# MCU.net
KiCad netlist of a schematic drawn in Altium Designer
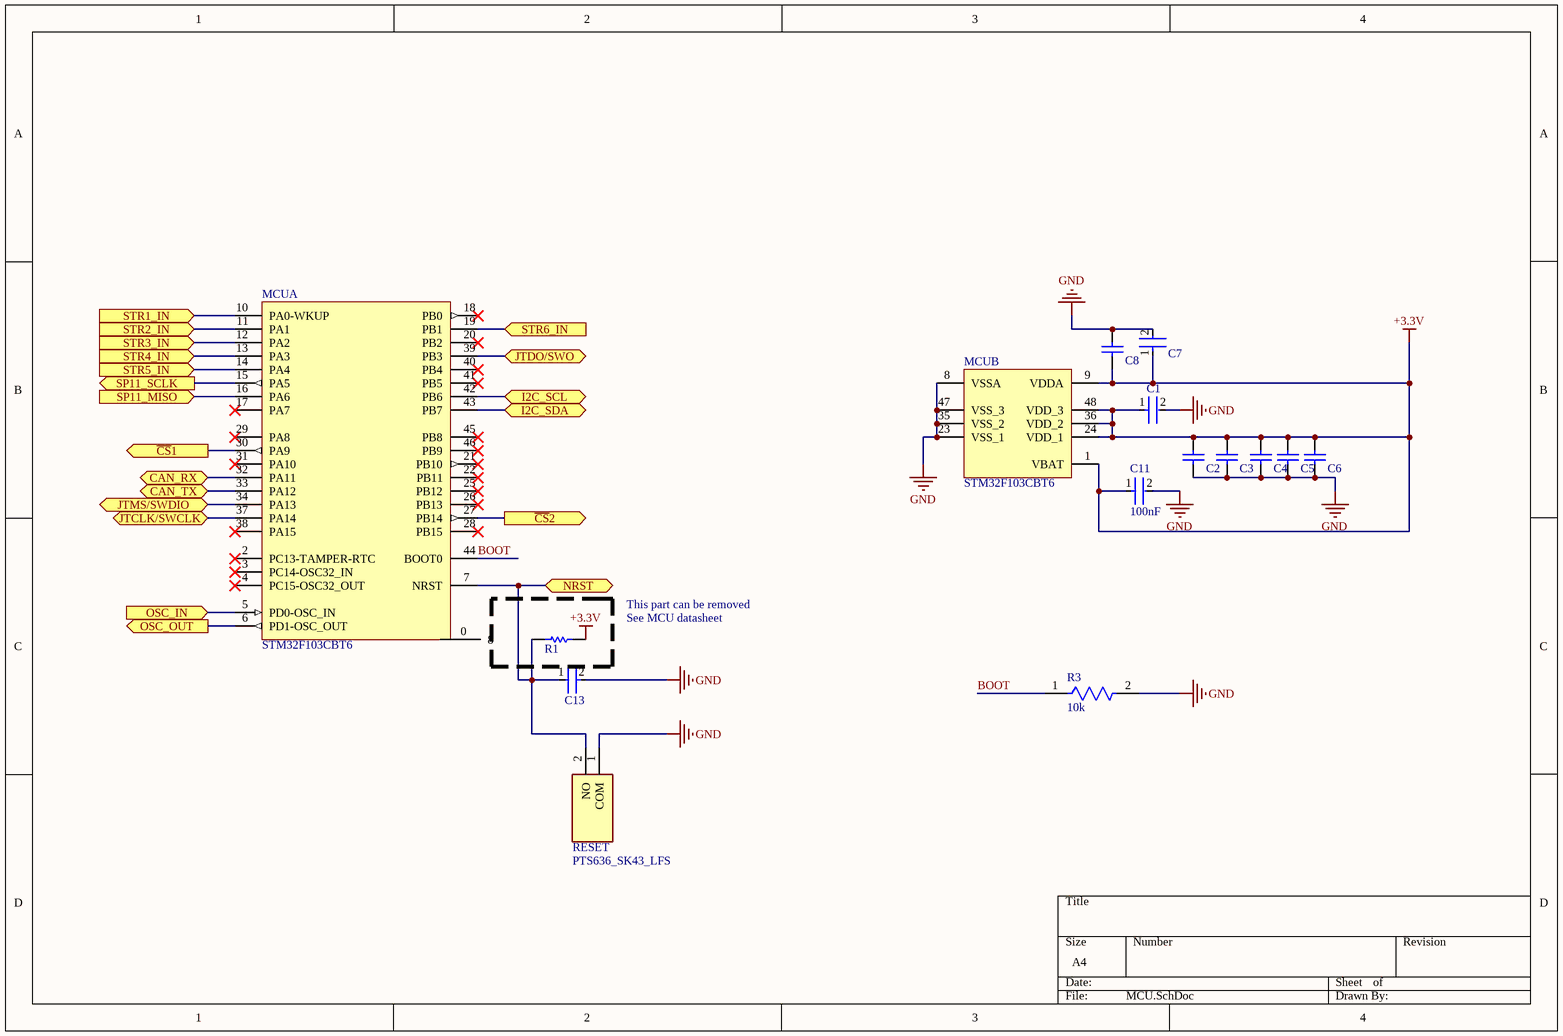
[diagram p0: MCU.SchDoc]

(export (version "E")
  (design (tool "Eeschema 10.0.6"))
  (components
    (comp (ref "C1")
      (value "GRM155R60J475ME47D")
      (footprint "FP-GRM155-0_1-IPC_B")
      (description "Chip Multilayer Ceramic Capacitors for General Purpose, 0402, 4.7uF, X5R, 15%, 20%, 6.3V")
      (fields (field (name "VOLTAGE") "6.3V") (field (name "TOLERANCE") "20%"))
      (libsource (lib "Altium Content Vault") (part "11868f565c42a9108669ba33697ecf6"))
    )
    (comp (ref "C2")
      (value "08051C104KAT2A")
      (footprint "CAPC2013X94X50ML20T25")
      (fields (field (name "MANUFACTURER") "AVX Interconnect / Elco"))
      (libsource (lib "Altium Content Vault") (part "CAP"))
    )
    (comp (ref "C3")
      (value "08051C104KAT2A")
      (footprint "CAPC2013X94X50ML20T25")
      (fields (field (name "MANUFACTURER") "AVX Interconnect / Elco"))
      (libsource (lib "Altium Content Vault") (part "CAP"))
    )
    (comp (ref "C4")
      (value "08051C104KAT2A")
      (footprint "CAPC2013X94X50ML20T25")
      (fields (field (name "MANUFACTURER") "AVX Interconnect / Elco"))
      (libsource (lib "Altium Content Vault") (part "CAP"))
    )
    (comp (ref "C5")
      (value "08051C104KAT2A")
      (footprint "CAPC2013X94X50ML20T25")
      (fields (field (name "MANUFACTURER") "AVX Interconnect / Elco"))
      (libsource (lib "Altium Content Vault") (part "CAP"))
    )
    (comp (ref "C6")
      (value "08051C104KAT2A")
      (footprint "CAPC2013X94X50ML20T25")
      (fields (field (name "MANUFACTURER") "AVX Interconnect / Elco"))
      (libsource (lib "Altium Content Vault") (part "CAP"))
    )
    (comp (ref "C7")
      (value "GRM155R61A105KE15D")
      (footprint "FP-GRM15-0_1-MFG")
      (description "CAP CER 1UF 10V X5R 0402")
      (fields
        (field (name "OCTOPART") "https://octopart.com/grm155r61a105ke15d-murata-197442")
        (field (name "MANUFACTURER") "Murata")
      )
      (libsource (lib "Altium Content Vault") (part "02cd4be3c70576c341d710602a673aa"))
    )
    (comp (ref "C8")
      (value "08051C104KAT2A")
      (footprint "CAPC2013X94X50ML20T25")
      (fields (field (name "MANUFACTURER") "AVX Interconnect / Elco"))
      (libsource (lib "Altium Content Vault") (part "CAP"))
    )
    (comp (ref "C11")
      (value "100nF")
      (footprint "FP-C0402-BB-MFG")
      (description "CAP CER 0.1UF 10V X5R 0402")
      (fields (field (name "MANUFACTURER") "Kemet") (field (name "TOLERANCE") "0.1"))
      (libsource (lib "Altium Content Vault") (part "b4654b650e69147ec39a6b967a45e02"))
    )
    (comp (ref "C13")
      (value "GRM155R71C104KA88D")
      (footprint "FP-GRM15-MFG")
      (description "CAP CER 0.1UF 16V X7R 0402")
      (fields
        (field (name "TOLERANCE") "10%")
        (field (name "OCTOPART") "https://octopart.com/grm155r71c104ka88d-murata-196880")
      )
      (libsource (lib "Altium Content Vault") (part "236180d848d6139a670b325ea6854c9"))
    )
    (comp (ref "MCU")
      (value "STM32F103CBT6")
      (footprint "STM-LQFP48_L")
      (libsource (lib "") (part "MC-ARM-STM32F103X8_B-SQ48_1"))
    )
    (comp (ref "R1")
      (value "CRCW12064K70FKEA")
      (footprint "RESC3216X60X45ML15T20")
      (description "Chip Resistor, 4.7 KOhm, +/- 1%, 0.25 W, -55 to 155 degC, 1206 (3216 Metric), RoHS, Tape and Reel")
      (fields (field (name "MANUFACTURER") "Vishay Semiconductor") (field (name "TOLERANCE") "1%"))
      (libsource (lib "Altium Content Vault") (part "RES-2"))
    )
    (comp (ref "R3")
      (value "10k")
      (footprint "FP-CRCW0402-e3-IPC_B")
      (description "RES SMD 10K OHM 1% 1/16W 0402")
      (fields (field (name "TOLERANCE") "1%"))
      (libsource (lib "Altium Content Vault") (part "1029c3af85768c4190bb7ad29bc67b5"))
    )
    (comp (ref "RESET")
      (value "PTS636_SK43_LFS")
      (footprint "SamacSys:PTS636SK43LFS")
      (description "Switch")
      (fields (field (name "MANUFACTURER_PART_NUMBER") "PTS636 SK43 LFS"))
      (libsource (lib "*") (part "PTS636_SK43_LFS"))
    )
  )
  (nets
    (net (code "1") (name "+3.3V") (class "Default")
      (node (ref "C1") (pin "1") (pinfunction "1_1") (pintype "passive"))
      (node (ref "C11") (pin "1") (pinfunction "1_1") (pintype "passive"))
      (node (ref "C2") (pin "2") (pinfunction "2_2") (pintype "passive"))
      (node (ref "C3") (pin "2") (pinfunction "2_2") (pintype "passive"))
      (node (ref "C4") (pin "2") (pinfunction "2_2") (pintype "passive"))
      (node (ref "C5") (pin "2") (pinfunction "2_2") (pintype "passive"))
      (node (ref "C6") (pin "2") (pinfunction "2_2") (pintype "passive"))
      (node (ref "C7") (pin "1") (pinfunction "1_1") (pintype "passive"))
      (node (ref "C8") (pin "2") (pinfunction "2_2") (pintype "passive"))
      (node (ref "MCU") (pin "1") (pinfunction "VBAT_1") (pintype "power_in"))
      (node (ref "MCU") (pin "24") (pinfunction "VDD_1_24") (pintype "power_in"))
      (node (ref "MCU") (pin "36") (pinfunction "VDD_2_36") (pintype "power_in"))
      (node (ref "MCU") (pin "48") (pinfunction "VDD_3_48") (pintype "power_in"))
      (node (ref "MCU") (pin "9") (pinfunction "VDDA_9") (pintype "power_in"))
      (node (ref "R1") (pin "2") (pinfunction "2_2") (pintype "passive"))
    )
    (net (code "2") (name "/BOOT") (class "Default")
      (node (ref "MCU") (pin "44") (pinfunction "BOOT0_44") (pintype "passive"))
      (node (ref "R3") (pin "1") (pinfunction "1_1") (pintype "passive"))
    )
    (net (code "3") (name "/CAN_RX") (class "Default")
      (node (ref "MCU") (pin "32") (pinfunction "PA11_32") (pintype "passive"))
    )
    (net (code "4") (name "/CAN_TX") (class "Default")
      (node (ref "MCU") (pin "33") (pinfunction "PA12_33") (pintype "passive"))
    )
    (net (code "5") (name "/I2C_SCL") (class "Default")
      (node (ref "MCU") (pin "42") (pinfunction "PB6_42") (pintype "passive"))
    )
    (net (code "6") (name "/I2C_SDA") (class "Default")
      (node (ref "MCU") (pin "43") (pinfunction "PB7_43") (pintype "passive"))
    )
    (net (code "7") (name "/JTCLK{slash}SWCLK") (class "Default")
      (node (ref "MCU") (pin "37") (pinfunction "PA14_37") (pintype "passive"))
    )
    (net (code "8") (name "/JTDO{slash}SWO") (class "Default")
      (node (ref "MCU") (pin "39") (pinfunction "PB3_39") (pintype "passive"))
    )
    (net (code "9") (name "/JTMS{slash}SWDIO") (class "Default")
      (node (ref "MCU") (pin "34") (pinfunction "PA13_34") (pintype "passive"))
    )
    (net (code "10") (name "/NRST") (class "Default")
      (node (ref "C13") (pin "1") (pinfunction "1_1") (pintype "passive"))
      (node (ref "MCU") (pin "7") (pinfunction "NRST_7") (pintype "passive"))
      (node (ref "R1") (pin "1") (pinfunction "1_1") (pintype "passive"))
      (node (ref "RESET") (pin "2") (pinfunction "NO_2") (pintype "passive"))
    )
    (net (code "11") (name "/OSC_IN") (class "Default")
      (node (ref "MCU") (pin "5") (pinfunction "PD0-OSC_IN_5") (pintype "input"))
    )
    (net (code "12") (name "/OSC_OUT") (class "Default")
      (node (ref "MCU") (pin "6") (pinfunction "PD1-OSC_OUT_6") (pintype "output"))
    )
    (net (code "13") (name "/SP11_MISO") (class "Default")
      (node (ref "MCU") (pin "16") (pinfunction "PA6_16") (pintype "passive"))
    )
    (net (code "14") (name "/SP11_SCLK") (class "Default")
      (node (ref "MCU") (pin "15") (pinfunction "PA5_15") (pintype "output"))
    )
    (net (code "15") (name "/STR1_IN") (class "Default")
      (node (ref "MCU") (pin "10") (pinfunction "PA0-WKUP_10") (pintype "passive"))
    )
    (net (code "16") (name "/STR2_IN") (class "Default")
      (node (ref "MCU") (pin "11") (pinfunction "PA1_11") (pintype "passive"))
    )
    (net (code "17") (name "/STR3_IN") (class "Default")
      (node (ref "MCU") (pin "12") (pinfunction "PA2_12") (pintype "passive"))
    )
    (net (code "18") (name "/STR4_IN") (class "Default")
      (node (ref "MCU") (pin "13") (pinfunction "PA3_13") (pintype "passive"))
    )
    (net (code "19") (name "/STR5_IN") (class "Default")
      (node (ref "MCU") (pin "14") (pinfunction "PA4_14") (pintype "passive"))
    )
    (net (code "20") (name "/STR6_IN") (class "Default")
      (node (ref "MCU") (pin "19") (pinfunction "PB1_19") (pintype "passive"))
    )
    (net (code "21") (name "/~{CS}1") (class "Default")
      (node (ref "MCU") (pin "30") (pinfunction "PA9_30") (pintype "output"))
    )
    (net (code "22") (name "/~{CS}2") (class "Default")
      (node (ref "MCU") (pin "27") (pinfunction "PB14_27") (pintype "output"))
    )
    (net (code "23") (name "GND") (class "Default")
      (node (ref "C1") (pin "2") (pinfunction "2_2") (pintype "passive"))
      (node (ref "C11") (pin "2") (pinfunction "2_2") (pintype "passive"))
      (node (ref "C13") (pin "2") (pinfunction "2_2") (pintype "passive"))
      (node (ref "C2") (pin "1") (pinfunction "1_1") (pintype "passive"))
      (node (ref "C3") (pin "1") (pinfunction "1_1") (pintype "passive"))
      (node (ref "C4") (pin "1") (pinfunction "1_1") (pintype "passive"))
      (node (ref "C5") (pin "1") (pinfunction "1_1") (pintype "passive"))
      (node (ref "C6") (pin "1") (pinfunction "1_1") (pintype "passive"))
      (node (ref "C7") (pin "2") (pinfunction "2_2") (pintype "passive"))
      (node (ref "C8") (pin "1") (pinfunction "1_1") (pintype "passive"))
      (node (ref "MCU") (pin "23") (pinfunction "VSS_1_23") (pintype "power_in"))
      (node (ref "MCU") (pin "35") (pinfunction "VSS_2_35") (pintype "power_in"))
      (node (ref "MCU") (pin "47") (pinfunction "VSS_3_47") (pintype "power_in"))
      (node (ref "MCU") (pin "8") (pinfunction "VSSA_8") (pintype "power_in"))
      (node (ref "R3") (pin "2") (pinfunction "2_2") (pintype "passive"))
      (node (ref "RESET") (pin "1") (pinfunction "COM_1") (pintype "passive"))
    )
    (net (code "24") (name "unconnected-(MCUA-8-Pad0)") (class "Default")
      (node (ref "MCU") (pin "0") (pinfunction "8_0") (pintype "passive"))
    )
    (net (code "25") (name "unconnected-(MCUA-PA7-Pad17)") (class "Default")
      (node (ref "MCU") (pin "17") (pinfunction "PA7_17") (pintype "passive+no_connect"))
    )
    (net (code "26") (name "unconnected-(MCUA-PA8-Pad29)") (class "Default")
      (node (ref "MCU") (pin "29") (pinfunction "PA8_29") (pintype "passive+no_connect"))
    )
    (net (code "27") (name "unconnected-(MCUA-PA10-Pad31)") (class "Default")
      (node (ref "MCU") (pin "31") (pinfunction "PA10_31") (pintype "passive+no_connect"))
    )
    (net (code "28") (name "unconnected-(MCUA-PA15-Pad38)") (class "Default")
      (node (ref "MCU") (pin "38") (pinfunction "PA15_38") (pintype "passive+no_connect"))
    )
    (net (code "29") (name "unconnected-(MCUA-PB0-Pad18)") (class "Default")
      (node (ref "MCU") (pin "18") (pinfunction "PB0_18") (pintype "output+no_connect"))
    )
    (net (code "30") (name "unconnected-(MCUA-PB2-Pad20)") (class "Default")
      (node (ref "MCU") (pin "20") (pinfunction "PB2_20") (pintype "passive+no_connect"))
    )
    (net (code "31") (name "unconnected-(MCUA-PB4-Pad40)") (class "Default")
      (node (ref "MCU") (pin "40") (pinfunction "PB4_40") (pintype "passive+no_connect"))
    )
    (net (code "32") (name "unconnected-(MCUA-PB5-Pad41)") (class "Default")
      (node (ref "MCU") (pin "41") (pinfunction "PB5_41") (pintype "passive+no_connect"))
    )
    (net (code "33") (name "unconnected-(MCUA-PB8-Pad45)") (class "Default")
      (node (ref "MCU") (pin "45") (pinfunction "PB8_45") (pintype "passive+no_connect"))
    )
    (net (code "34") (name "unconnected-(MCUA-PB9-Pad46)") (class "Default")
      (node (ref "MCU") (pin "46") (pinfunction "PB9_46") (pintype "passive+no_connect"))
    )
    (net (code "35") (name "unconnected-(MCUA-PB10-Pad21)") (class "Default")
      (node (ref "MCU") (pin "21") (pinfunction "PB10_21") (pintype "output+no_connect"))
    )
    (net (code "36") (name "unconnected-(MCUA-PB11-Pad22)") (class "Default")
      (node (ref "MCU") (pin "22") (pinfunction "PB11_22") (pintype "passive+no_connect"))
    )
    (net (code "37") (name "unconnected-(MCUA-PB12-Pad25)") (class "Default")
      (node (ref "MCU") (pin "25") (pinfunction "PB12_25") (pintype "passive+no_connect"))
    )
    (net (code "38") (name "unconnected-(MCUA-PB13-Pad26)") (class "Default")
      (node (ref "MCU") (pin "26") (pinfunction "PB13_26") (pintype "passive+no_connect"))
    )
    (net (code "39") (name "unconnected-(MCUA-PB15-Pad28)") (class "Default")
      (node (ref "MCU") (pin "28") (pinfunction "PB15_28") (pintype "passive+no_connect"))
    )
    (net (code "40") (name "unconnected-(MCUA-PC13-TAMPER-RTC-Pad2)") (class "Default")
      (node (ref "MCU") (pin "2") (pinfunction "PC13-TAMPER-RTC_2") (pintype "passive+no_connect"))
    )
    (net (code "41") (name "unconnected-(MCUA-PC14-OSC32_IN-Pad3)") (class "Default")
      (node (ref "MCU") (pin "3") (pinfunction "PC14-OSC32_IN_3") (pintype "passive+no_connect"))
    )
    (net (code "42") (name "unconnected-(MCUA-PC15-OSC32_OUT-Pad4)") (class "Default")
      (node (ref "MCU") (pin "4") (pinfunction "PC15-OSC32_OUT_4") (pintype "passive+no_connect"))
    )
  )
)
